# SL_LCD_SW_LED_2E.net
KiCad netlist of a schematic drawn in Altium Designer
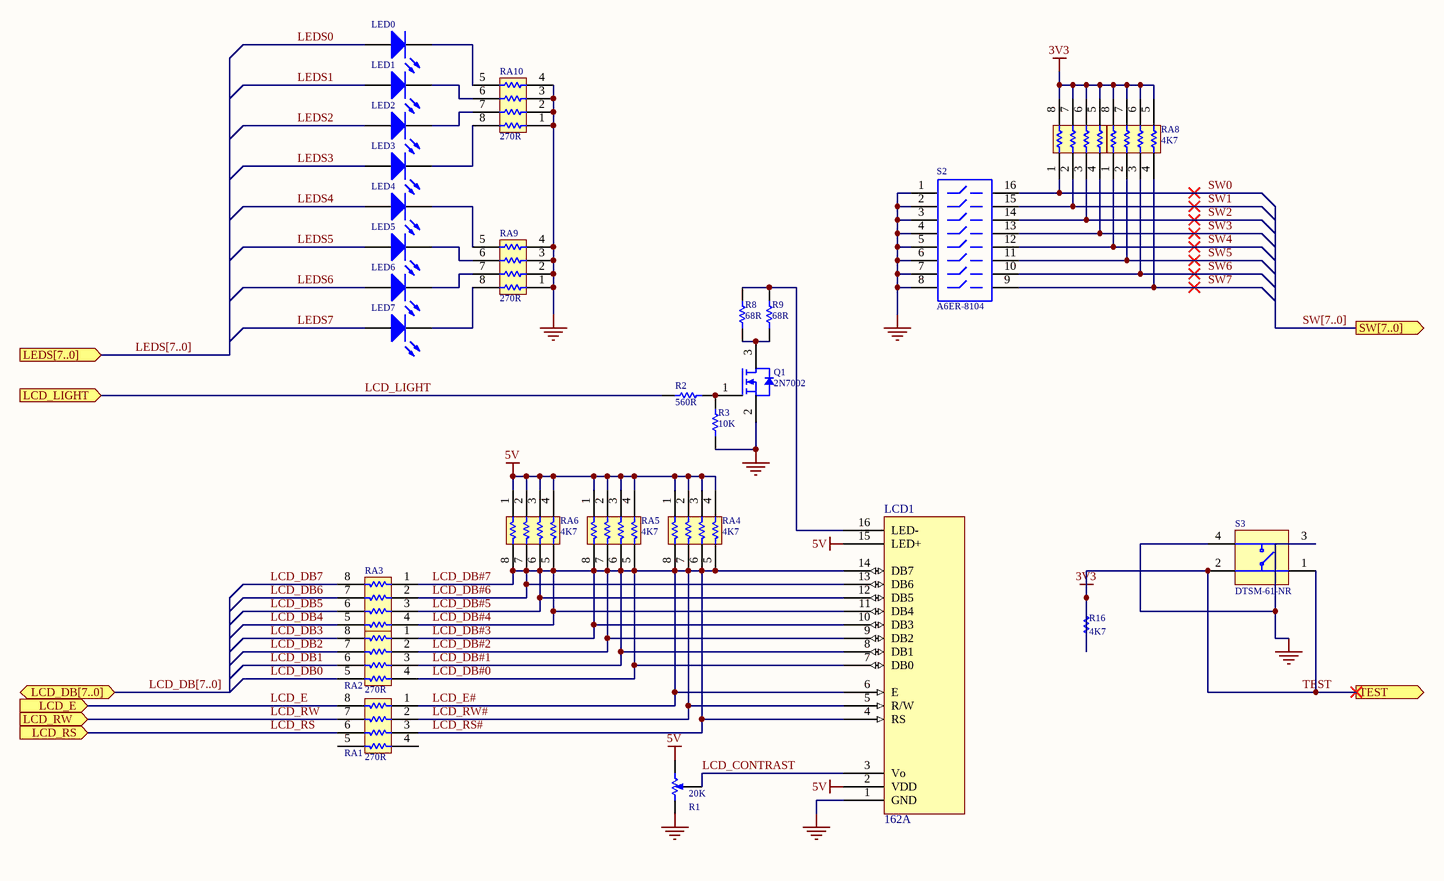
[diagram p0: SL_LCD_SW_LED_2E.SchDoc]

(export (version "E")
  (design (tool "Eeschema 10.0.6"))
  (components
    (comp (ref "LCD1")
      (value "162A")
      (footprint "Spirit_Level_Project:162A")
      (description "16 char * 2 line LCD character display with b/light")
      (libsource (lib "SpiritLevel_2E") (part "162A"))
    )
    (comp (ref "LED0")
      (value "HSMH-C170")
      (footprint "Spirit_Level_Project:SMD _LED")
      (description "Typical RED GaAs SMD LED Agilent make")
      (libsource (lib "SpiritLevel_2E") (part "HSMX-C670"))
    )
    (comp (ref "LED1")
      (value "HSMH-C170")
      (footprint "Spirit_Level_Project:SMD _LED")
      (description "Typical RED GaAs SMD LED Agilent make")
      (libsource (lib "SpiritLevel_2E") (part "HSMX-C670"))
    )
    (comp (ref "LED2")
      (value "HSMH-C170")
      (footprint "Spirit_Level_Project:SMD _LED")
      (description "Typical RED GaAs SMD LED Agilent make")
      (libsource (lib "SpiritLevel_2E") (part "HSMX-C670"))
    )
    (comp (ref "LED3")
      (value "HSMH-C170")
      (footprint "Spirit_Level_Project:SMD _LED")
      (description "Typical RED GaAs SMD LED Agilent make")
      (libsource (lib "SpiritLevel_2E") (part "HSMX-C670"))
    )
    (comp (ref "LED4")
      (value "HSMH-C170")
      (footprint "Spirit_Level_Project:SMD _LED")
      (description "Typical RED GaAs SMD LED Agilent make")
      (libsource (lib "SpiritLevel_2E") (part "HSMX-C670"))
    )
    (comp (ref "LED5")
      (value "HSMH-C170")
      (footprint "Spirit_Level_Project:SMD _LED")
      (description "Typical RED GaAs SMD LED Agilent make")
      (libsource (lib "SpiritLevel_2E") (part "HSMX-C670"))
    )
    (comp (ref "LED6")
      (value "HSMH-C170")
      (footprint "Spirit_Level_Project:SMD _LED")
      (description "Typical RED GaAs SMD LED Agilent make")
      (libsource (lib "SpiritLevel_2E") (part "HSMX-C670"))
    )
    (comp (ref "LED7")
      (value "HSMH-C170")
      (footprint "Spirit_Level_Project:SMD _LED")
      (description "Typical RED GaAs SMD LED Agilent make")
      (libsource (lib "SpiritLevel_2E") (part "HSMX-C670"))
    )
    (comp (ref "Q1")
      (value "2N7002")
      (footprint "Spirit_Level_Project:SO-G3")
      (description "N Channel Mosfet")
      (libsource (lib "SpiritLevel_2E") (part "2N7002"))
    )
    (comp (ref "R1")
      (value "20K")
      (footprint "Spirit_Level_Project:POT4MM-2")
      (description "Square Trimming Potentiometer")
      (libsource (lib "SpiritLevel_2E") (part "RPot SM"))
    )
    (comp (ref "R2")
      (value "560R")
      (footprint "CC2012-0805")
      (description "Resistor")
      (libsource (lib "SpiritLevel_2E") (part "RES"))
    )
    (comp (ref "R3")
      (value "10K")
      (footprint "CC2012-0805")
      (description "Resistor")
      (libsource (lib "SpiritLevel_2E") (part "RES"))
    )
    (comp (ref "R8")
      (value "68R")
      (footprint "CC2012-0805")
      (description "Resistor")
      (libsource (lib "") (part "RES_1"))
    )
    (comp (ref "R9")
      (value "68R")
      (footprint "CC2012-0805")
      (description "Resistor")
      (libsource (lib "") (part "RES_1"))
    )
    (comp (ref "R16")
      (value "4K7")
      (footprint "CC2012-0805")
      (description "Resistor")
      (libsource (lib "SpiritLevel_2E") (part "RES"))
    )
    (comp (ref "RA1")
      (value "270R")
      (footprint "Spirit_Level_Project:MNR34")
      (description "3216x4 Resistor Array")
      (libsource (lib "") (part "MNR34_3"))
    )
    (comp (ref "RA2")
      (value "270R")
      (footprint "Spirit_Level_Project:MNR34")
      (description "3216x4 Resistor Array")
      (libsource (lib "") (part "MNR34_3"))
    )
    (comp (ref "RA3")
      (value "270R")
      (footprint "Spirit_Level_Project:MNR34")
      (description "3216x4 Resistor Array")
      (libsource (lib "") (part "MNR34_3"))
    )
    (comp (ref "RA4")
      (value "4K7")
      (footprint "Spirit_Level_Project:MNR34T")
      (description "3216x4 Resistor Array")
      (libsource (lib "") (part "MNR34_1"))
    )
    (comp (ref "RA5")
      (value "4K7")
      (footprint "Spirit_Level_Project:MNR34T")
      (description "3216x4 Resistor Array")
      (libsource (lib "") (part "MNR34_1"))
    )
    (comp (ref "RA6")
      (value "4K7")
      (footprint "Spirit_Level_Project:MNR34T")
      (description "3216x4 Resistor Array")
      (libsource (lib "") (part "MNR34_1"))
    )
    (comp (ref "RA7")
      (value "4K7")
      (footprint "Spirit_Level_Project:MNR34T")
      (description "3216x4 Resistor Array")
      (libsource (lib "") (part "MNR34_2"))
    )
    (comp (ref "RA8")
      (value "4K7")
      (footprint "Spirit_Level_Project:MNR34T")
      (description "3216x4 Resistor Array")
      (libsource (lib "") (part "MNR34_2"))
    )
    (comp (ref "RA9")
      (value "270R")
      (footprint "Spirit_Level_Project:MNR34T")
      (description "3216x4 Resistor Array")
      (libsource (lib "SpiritLevel_2E") (part "MNR34"))
    )
    (comp (ref "RA10")
      (value "270R")
      (footprint "Spirit_Level_Project:MNR34T")
      (description "3216x4 Resistor Array")
      (libsource (lib "SpiritLevel_2E") (part "MNR34"))
    )
    (comp (ref "S2")
      (value "A6ER-8104")
      (footprint "Spirit_Level_Project:DIP-16-KEY")
      (description "DIP Switch Side actuator long liver Piano Key")
      (libsource (lib "SpiritLevel_2E") (part "A6ER-8104"))
    )
    (comp (ref "S3")
      (value "DTSM-61-NR")
      (footprint "Spirit_Level_Project:B3FS_SWITCH")
      (description "SPNA SMD Keyboard Switch")
      (libsource (lib "SpiritLevel_2E") (part "B3FS"))
    )
  )
  (nets
    (net (code "1") (name "/LCD_CONTRAST") (class "Default")
      (node (ref "LCD1") (pin "3") (pinfunction "Vo_3") (pintype "tri_state"))
      (node (ref "R1") (pin "W") (pintype "passive"))
    )
    (net (code "2") (name "/LCD_DB#0") (class "Default")
      (node (ref "LCD1") (pin "10") (pinfunction "DB3_10") (pintype "bidirectional"))
      (node (ref "LCD1") (pin "11") (pinfunction "DB4_11") (pintype "bidirectional"))
      (node (ref "LCD1") (pin "12") (pinfunction "DB5_12") (pintype "bidirectional"))
      (node (ref "LCD1") (pin "13") (pinfunction "DB6_13") (pintype "bidirectional"))
      (node (ref "LCD1") (pin "14") (pinfunction "DB7_14") (pintype "bidirectional"))
      (node (ref "LCD1") (pin "4") (pinfunction "RS_4") (pintype "input"))
      (node (ref "LCD1") (pin "5") (pinfunction "R/W_5") (pintype "input"))
      (node (ref "LCD1") (pin "6") (pinfunction "E_6") (pintype "input"))
      (node (ref "LCD1") (pin "7") (pinfunction "DB0_7") (pintype "bidirectional"))
      (node (ref "LCD1") (pin "8") (pinfunction "DB1_8") (pintype "bidirectional"))
      (node (ref "LCD1") (pin "9") (pinfunction "DB2_9") (pintype "bidirectional"))
      (node (ref "RA1") (pin "1") (pintype "passive"))
      (node (ref "RA1") (pin "2") (pintype "passive"))
      (node (ref "RA1") (pin "3") (pintype "passive"))
      (node (ref "RA2") (pin "1") (pintype "passive"))
      (node (ref "RA2") (pin "2") (pintype "passive"))
      (node (ref "RA2") (pin "3") (pintype "passive"))
      (node (ref "RA2") (pin "4") (pintype "passive"))
      (node (ref "RA3") (pin "1") (pintype "passive"))
      (node (ref "RA3") (pin "2") (pintype "passive"))
      (node (ref "RA3") (pin "3") (pintype "passive"))
      (node (ref "RA3") (pin "4") (pintype "passive"))
      (node (ref "RA4") (pin "5") (pintype "passive"))
      (node (ref "RA4") (pin "6") (pintype "passive"))
      (node (ref "RA4") (pin "7") (pintype "passive"))
      (node (ref "RA4") (pin "8") (pintype "passive"))
      (node (ref "RA5") (pin "5") (pintype "passive"))
      (node (ref "RA5") (pin "6") (pintype "passive"))
      (node (ref "RA5") (pin "7") (pintype "passive"))
      (node (ref "RA5") (pin "8") (pintype "passive"))
      (node (ref "RA6") (pin "5") (pintype "passive"))
      (node (ref "RA6") (pin "6") (pintype "passive"))
      (node (ref "RA6") (pin "7") (pintype "passive"))
      (node (ref "RA6") (pin "8") (pintype "passive"))
    )
    (net (code "3") (name "/LCD_DB0") (class "Default") (node (ref "RA2") (pin "5") (pintype "passive")))
    (net (code "4") (name "/LCD_DB1") (class "Default") (node (ref "RA2") (pin "6") (pintype "passive")))
    (net (code "5") (name "/LCD_DB2") (class "Default") (node (ref "RA2") (pin "7") (pintype "passive")))
    (net (code "6") (name "/LCD_DB3") (class "Default") (node (ref "RA2") (pin "8") (pintype "passive")))
    (net (code "7") (name "/LCD_DB4") (class "Default") (node (ref "RA3") (pin "5") (pintype "passive")))
    (net (code "8") (name "/LCD_DB5") (class "Default") (node (ref "RA3") (pin "6") (pintype "passive")))
    (net (code "9") (name "/LCD_DB6") (class "Default") (node (ref "RA3") (pin "7") (pintype "passive")))
    (net (code "10") (name "/LCD_DB7") (class "Default") (node (ref "RA3") (pin "8") (pintype "passive")))
    (net (code "12") (name "/LCD_E") (class "Default") (node (ref "RA1") (pin "8") (pintype "passive")))
    (net (code "13") (name "/LCD_LIGHT") (class "Default")
      (node (ref "R2") (pin "1") (pinfunction "1_1") (pintype "passive"))
    )
    (net (code "14") (name "/LCD_RS") (class "Default") (node (ref "RA1") (pin "6") (pintype "passive")))
    (net (code "15") (name "/LCD_RW") (class "Default") (node (ref "RA1") (pin "7") (pintype "passive")))
    (net (code "16") (name "/LEDS0") (class "Default")
      (node (ref "LED0") (pin "1") (pinfunction "A_1") (pintype "passive"))
    )
    (net (code "17") (name "/LEDS1") (class "Default")
      (node (ref "LED1") (pin "1") (pinfunction "A_1") (pintype "passive"))
    )
    (net (code "18") (name "/LEDS2") (class "Default")
      (node (ref "LED2") (pin "1") (pinfunction "A_1") (pintype "passive"))
    )
    (net (code "19") (name "/LEDS3") (class "Default")
      (node (ref "LED3") (pin "1") (pinfunction "A_1") (pintype "passive"))
    )
    (net (code "20") (name "/LEDS4") (class "Default")
      (node (ref "LED4") (pin "1") (pinfunction "A_1") (pintype "passive"))
    )
    (net (code "21") (name "/LEDS5") (class "Default")
      (node (ref "LED5") (pin "1") (pinfunction "A_1") (pintype "passive"))
    )
    (net (code "22") (name "/LEDS6") (class "Default")
      (node (ref "LED6") (pin "1") (pinfunction "A_1") (pintype "passive"))
    )
    (net (code "23") (name "/LEDS7") (class "Default")
      (node (ref "LED7") (pin "1") (pinfunction "A_1") (pintype "passive"))
    )
    (net (code "25") (name "/SW0") (class "Default")
      (node (ref "RA7") (pin "1") (pintype "passive"))
      (node (ref "S2") (pin "16") (pinfunction "16_16") (pintype "passive"))
    )
    (net (code "26") (name "/SW1") (class "Default")
      (node (ref "RA7") (pin "2") (pintype "passive"))
      (node (ref "S2") (pin "15") (pinfunction "15_15") (pintype "passive"))
    )
    (net (code "27") (name "/SW2") (class "Default")
      (node (ref "RA7") (pin "3") (pintype "passive"))
      (node (ref "S2") (pin "14") (pinfunction "14_14") (pintype "passive"))
    )
    (net (code "28") (name "/SW3") (class "Default")
      (node (ref "RA7") (pin "4") (pintype "passive"))
      (node (ref "S2") (pin "13") (pinfunction "13_13") (pintype "passive"))
    )
    (net (code "29") (name "/SW4") (class "Default")
      (node (ref "RA8") (pin "1") (pintype "passive"))
      (node (ref "S2") (pin "12") (pinfunction "12_12") (pintype "passive"))
    )
    (net (code "30") (name "/SW5") (class "Default")
      (node (ref "RA8") (pin "2") (pintype "passive"))
      (node (ref "S2") (pin "11") (pinfunction "11_11") (pintype "passive"))
    )
    (net (code "31") (name "/SW6") (class "Default")
      (node (ref "RA8") (pin "3") (pintype "passive"))
      (node (ref "S2") (pin "10") (pinfunction "10_10") (pintype "passive"))
    )
    (net (code "32") (name "/SW7") (class "Default")
      (node (ref "RA8") (pin "4") (pintype "passive"))
      (node (ref "S2") (pin "9") (pinfunction "9_9") (pintype "passive"))
    )
    (net (code "34") (name "3V3") (class "Default")
      (node (ref "R16") (pin "1") (pinfunction "1_1") (pintype "passive"))
      (node (ref "R16") (pin "2") (pinfunction "2_2") (pintype "passive"))
      (node (ref "RA7") (pin "5") (pintype "passive"))
      (node (ref "RA7") (pin "6") (pintype "passive"))
      (node (ref "RA7") (pin "7") (pintype "passive"))
      (node (ref "RA7") (pin "8") (pintype "passive"))
      (node (ref "RA8") (pin "5") (pintype "passive"))
      (node (ref "RA8") (pin "6") (pintype "passive"))
      (node (ref "RA8") (pin "7") (pintype "passive"))
      (node (ref "RA8") (pin "8") (pintype "passive"))
      (node (ref "S3") (pin "1") (pinfunction "1_1") (pintype "passive"))
      (node (ref "S3") (pin "2") (pinfunction "2_2") (pintype "passive"))
    )
    (net (code "35") (name "5V") (class "Default")
      (node (ref "LCD1") (pin "15") (pinfunction "LED+_15") (pintype "power_in"))
      (node (ref "LCD1") (pin "2") (pinfunction "VDD_2") (pintype "power_in"))
      (node (ref "R1") (pin "CW") (pinfunction "+_CW") (pintype "passive"))
      (node (ref "RA4") (pin "1") (pintype "passive"))
      (node (ref "RA4") (pin "2") (pintype "passive"))
      (node (ref "RA4") (pin "3") (pintype "passive"))
      (node (ref "RA4") (pin "4") (pintype "passive"))
      (node (ref "RA5") (pin "1") (pintype "passive"))
      (node (ref "RA5") (pin "2") (pintype "passive"))
      (node (ref "RA5") (pin "3") (pintype "passive"))
      (node (ref "RA5") (pin "4") (pintype "passive"))
      (node (ref "RA6") (pin "1") (pintype "passive"))
      (node (ref "RA6") (pin "2") (pintype "passive"))
      (node (ref "RA6") (pin "3") (pintype "passive"))
      (node (ref "RA6") (pin "4") (pintype "passive"))
    )
    (net (code "36") (name "GND") (class "Default")
      (node (ref "LCD1") (pin "1") (pinfunction "GND_1") (pintype "power_in"))
      (node (ref "Q1") (pin "2") (pintype "passive"))
      (node (ref "R1") (pin "CCW") (pinfunction "-_CCW") (pintype "passive"))
      (node (ref "R3") (pin "1") (pinfunction "1_1") (pintype "passive"))
      (node (ref "RA10") (pin "1") (pintype "passive"))
      (node (ref "RA10") (pin "2") (pintype "passive"))
      (node (ref "RA10") (pin "3") (pintype "passive"))
      (node (ref "RA10") (pin "4") (pintype "passive"))
      (node (ref "RA9") (pin "1") (pintype "passive"))
      (node (ref "RA9") (pin "2") (pintype "passive"))
      (node (ref "RA9") (pin "3") (pintype "passive"))
      (node (ref "RA9") (pin "4") (pintype "passive"))
      (node (ref "S2") (pin "1") (pinfunction "1_1") (pintype "passive"))
      (node (ref "S2") (pin "2") (pinfunction "2_2") (pintype "passive"))
      (node (ref "S2") (pin "3") (pinfunction "3_3") (pintype "passive"))
      (node (ref "S2") (pin "4") (pinfunction "4_4") (pintype "passive"))
      (node (ref "S2") (pin "5") (pinfunction "5_5") (pintype "passive"))
      (node (ref "S2") (pin "6") (pinfunction "6_6") (pintype "passive"))
      (node (ref "S2") (pin "7") (pinfunction "7_7") (pintype "passive"))
      (node (ref "S2") (pin "8") (pinfunction "8_8") (pintype "passive"))
      (node (ref "S3") (pin "3") (pinfunction "3_3") (pintype "passive"))
      (node (ref "S3") (pin "4") (pinfunction "4_4") (pintype "passive"))
    )
    (net (code "37") (name "Net-(LCD1-LED-)") (class "Default")
      (node (ref "LCD1") (pin "16") (pinfunction "LED-_16") (pintype "power_in"))
      (node (ref "R8") (pin "1") (pinfunction "1_1") (pintype "passive"))
      (node (ref "R9") (pin "1") (pinfunction "1_1") (pintype "passive"))
    )
    (net (code "38") (name "Net-(LED0-K)") (class "Default")
      (node (ref "LED0") (pin "2") (pinfunction "K_2") (pintype "passive"))
      (node (ref "RA10") (pin "5") (pintype "passive"))
    )
    (net (code "39") (name "Net-(LED1-K)") (class "Default")
      (node (ref "LED1") (pin "2") (pinfunction "K_2") (pintype "passive"))
      (node (ref "RA10") (pin "6") (pintype "passive"))
    )
    (net (code "40") (name "Net-(LED2-K)") (class "Default")
      (node (ref "LED2") (pin "2") (pinfunction "K_2") (pintype "passive"))
      (node (ref "RA10") (pin "7") (pintype "passive"))
    )
    (net (code "41") (name "Net-(LED3-K)") (class "Default")
      (node (ref "LED3") (pin "2") (pinfunction "K_2") (pintype "passive"))
      (node (ref "RA10") (pin "8") (pintype "passive"))
    )
    (net (code "42") (name "Net-(LED4-K)") (class "Default")
      (node (ref "LED4") (pin "2") (pinfunction "K_2") (pintype "passive"))
      (node (ref "RA9") (pin "5") (pintype "passive"))
    )
    (net (code "43") (name "Net-(LED5-K)") (class "Default")
      (node (ref "LED5") (pin "2") (pinfunction "K_2") (pintype "passive"))
      (node (ref "RA9") (pin "6") (pintype "passive"))
    )
    (net (code "44") (name "Net-(LED6-K)") (class "Default")
      (node (ref "LED6") (pin "2") (pinfunction "K_2") (pintype "passive"))
      (node (ref "RA9") (pin "7") (pintype "passive"))
    )
    (net (code "45") (name "Net-(LED7-K)") (class "Default")
      (node (ref "LED7") (pin "2") (pinfunction "K_2") (pintype "passive"))
      (node (ref "RA9") (pin "8") (pintype "passive"))
    )
    (net (code "46") (name "Net-(Q1-Pad1)") (class "Default")
      (node (ref "Q1") (pin "1") (pintype "passive"))
      (node (ref "R2") (pin "2") (pinfunction "2_2") (pintype "passive"))
      (node (ref "R3") (pin "2") (pinfunction "2_2") (pintype "passive"))
    )
    (net (code "47") (name "Net-(Q1-Pad3)") (class "Default")
      (node (ref "Q1") (pin "3") (pintype "passive"))
      (node (ref "R8") (pin "2") (pinfunction "2_2") (pintype "passive"))
      (node (ref "R9") (pin "2") (pinfunction "2_2") (pintype "passive"))
    )
    (net (code "48") (name "unconnected-(RA1-Pad4)") (class "Default")
      (node (ref "RA1") (pin "4") (pintype "passive"))
    )
    (net (code "49") (name "unconnected-(RA1-Pad5)") (class "Default")
      (node (ref "RA1") (pin "5") (pintype "passive"))
    )
  )
)
